# DSO_CPLD.net
KiCad netlist of a schematic drawn in Altium Designer
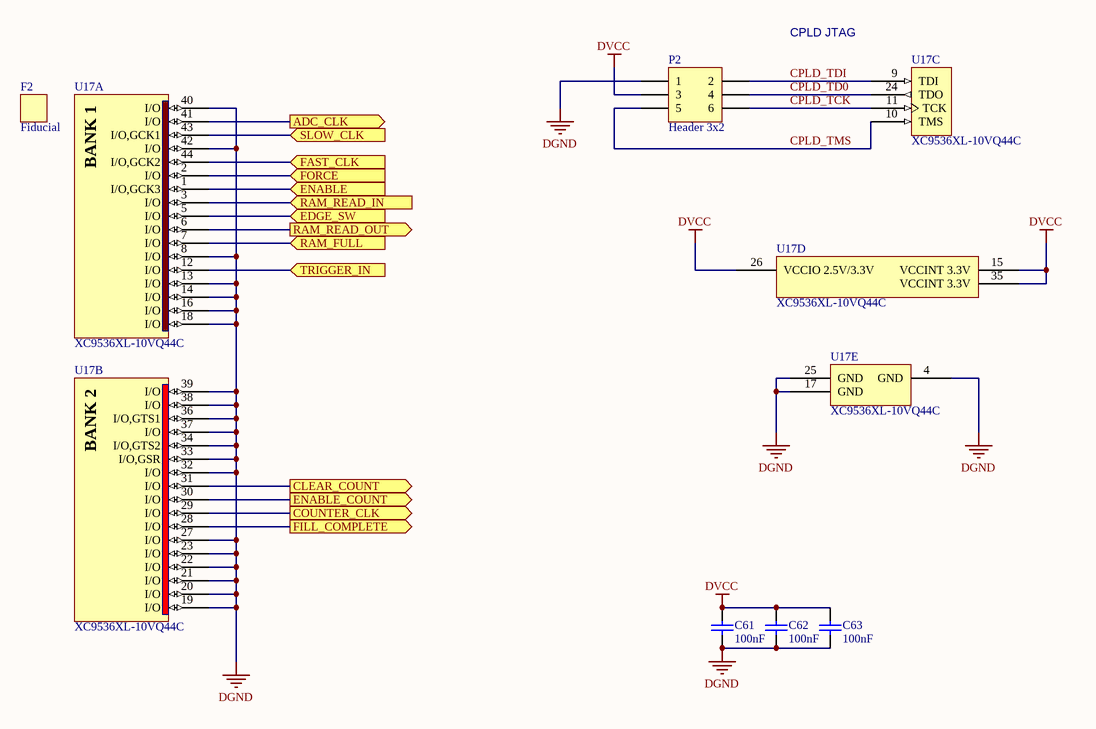
[diagram p0: DSO_CPLD.SchDoc]

(export (version "E")
  (design (tool "Eeschema 10.0.6"))
  (components
    (comp (ref "C61")
      (value "100nF")
      (footprint "0805C")
      (description "Capacitor")
      (fields (field (name "REVIEWED BY") "RM - 2018/08/05"))
      (libsource (lib "DSO") (part "C"))
    )
    (comp (ref "C62")
      (value "100nF")
      (footprint "0805C")
      (description "Capacitor")
      (fields (field (name "REVIEWED BY") "RM - 2018/08/05"))
      (libsource (lib "DSO") (part "C"))
    )
    (comp (ref "C63")
      (value "100nF")
      (footprint "0805C")
      (description "Capacitor")
      (fields (field (name "REVIEWED BY") "RM - 2018/08/05"))
      (libsource (lib "DSO") (part "C"))
    )
    (comp (ref "F2")
      (value "Fiducial")
      (footprint "FIDUCIAL")
      (description "Fiducial for pick and place machine")
      (libsource (lib "DSO") (part "Fiducial"))
    )
    (comp (ref "P2")
      (value "Header 3x2")
      (footprint "HDR3x2")
      (description "Header, 5-Pin")
      (fields (field (name "REVIEWED BY") "RM - 2018/08/05"))
      (libsource (lib "DSO") (part "Header 3x2"))
    )
    (comp (ref "U17")
      (value "XC9536XL-10VQ44C")
      (footprint "VQ44_L")
      (fields (field (name "REVIEWED BY") "RM - 2018/08/05"))
      (libsource (lib "DSO") (part "XC9536XL-10VQG44C"))
    )
  )
  (nets
    (net (code "1") (name "/ADC_CLK") (class "Default")
      (node (ref "U17") (pin "41") (pinfunction "I/O_41") (pintype "bidirectional"))
    )
    (net (code "2") (name "/CLEAR_COUNT") (class "Default")
      (node (ref "U17") (pin "31") (pinfunction "I/O_31") (pintype "bidirectional"))
    )
    (net (code "3") (name "/COUNTER_CLK") (class "Default")
      (node (ref "U17") (pin "29") (pinfunction "I/O_29") (pintype "bidirectional"))
    )
    (net (code "4") (name "/CPLD_TCK") (class "Default")
      (node (ref "P2") (pin "6") (pinfunction "6_6") (pintype "passive"))
      (node (ref "U17") (pin "11") (pinfunction "TCK_11") (pintype "input"))
    )
    (net (code "5") (name "/CPLD_TD0") (class "Default")
      (node (ref "P2") (pin "4") (pinfunction "4_4") (pintype "passive"))
      (node (ref "U17") (pin "24") (pinfunction "TDO_24") (pintype "output"))
    )
    (net (code "6") (name "/CPLD_TDI") (class "Default")
      (node (ref "P2") (pin "2") (pinfunction "2_2") (pintype "passive"))
      (node (ref "U17") (pin "9") (pinfunction "TDI_9") (pintype "input"))
    )
    (net (code "7") (name "/CPLD_TMS") (class "Default")
      (node (ref "P2") (pin "5") (pinfunction "5_5") (pintype "passive"))
      (node (ref "U17") (pin "10") (pinfunction "TMS_10") (pintype "input"))
    )
    (net (code "8") (name "/EDGE_SW") (class "Default")
      (node (ref "U17") (pin "5") (pinfunction "I/O_5") (pintype "bidirectional"))
    )
    (net (code "9") (name "/ENABLE") (class "Default")
      (node (ref "U17") (pin "1") (pinfunction "I/O,GCK3_1") (pintype "bidirectional"))
    )
    (net (code "10") (name "/ENABLE_COUNT") (class "Default")
      (node (ref "U17") (pin "30") (pinfunction "I/O_30") (pintype "bidirectional"))
    )
    (net (code "11") (name "/FAST_CLK") (class "Default")
      (node (ref "U17") (pin "44") (pinfunction "I/O,GCK2_44") (pintype "bidirectional"))
    )
    (net (code "12") (name "/FILL_COMPLETE") (class "Default")
      (node (ref "U17") (pin "28") (pinfunction "I/O_28") (pintype "bidirectional"))
    )
    (net (code "13") (name "/FORCE") (class "Default")
      (node (ref "U17") (pin "2") (pinfunction "I/O_2") (pintype "bidirectional"))
    )
    (net (code "14") (name "/RAM_FULL") (class "Default")
      (node (ref "U17") (pin "7") (pinfunction "I/O_7") (pintype "bidirectional"))
    )
    (net (code "15") (name "/RAM_READ_IN") (class "Default")
      (node (ref "U17") (pin "3") (pinfunction "I/O_3") (pintype "bidirectional"))
    )
    (net (code "16") (name "/RAM_READ_OUT") (class "Default")
      (node (ref "U17") (pin "6") (pinfunction "I/O_6") (pintype "bidirectional"))
    )
    (net (code "17") (name "/SLOW_CLK") (class "Default")
      (node (ref "U17") (pin "43") (pinfunction "I/O,GCK1_43") (pintype "bidirectional"))
    )
    (net (code "18") (name "/TRIGGER_IN") (class "Default")
      (node (ref "U17") (pin "12") (pinfunction "I/O_12") (pintype "bidirectional"))
    )
    (net (code "19") (name "DGND") (class "Default")
      (node (ref "C61") (pin "2") (pinfunction "2_2") (pintype "passive"))
      (node (ref "C62") (pin "2") (pinfunction "2_2") (pintype "passive"))
      (node (ref "C63") (pin "2") (pinfunction "2_2") (pintype "passive"))
      (node (ref "P2") (pin "1") (pinfunction "1_1") (pintype "passive"))
      (node (ref "U17") (pin "13") (pinfunction "I/O_13") (pintype "bidirectional"))
      (node (ref "U17") (pin "14") (pinfunction "I/O_14") (pintype "bidirectional"))
      (node (ref "U17") (pin "16") (pinfunction "I/O_16") (pintype "bidirectional"))
      (node (ref "U17") (pin "17") (pinfunction "GND_17") (pintype "power_in"))
      (node (ref "U17") (pin "18") (pinfunction "I/O_18") (pintype "bidirectional"))
      (node (ref "U17") (pin "19") (pinfunction "I/O_19") (pintype "bidirectional"))
      (node (ref "U17") (pin "20") (pinfunction "I/O_20") (pintype "bidirectional"))
      (node (ref "U17") (pin "21") (pinfunction "I/O_21") (pintype "bidirectional"))
      (node (ref "U17") (pin "22") (pinfunction "I/O_22") (pintype "bidirectional"))
      (node (ref "U17") (pin "23") (pinfunction "I/O_23") (pintype "bidirectional"))
      (node (ref "U17") (pin "25") (pinfunction "GND_25") (pintype "power_in"))
      (node (ref "U17") (pin "27") (pinfunction "I/O_27") (pintype "bidirectional"))
      (node (ref "U17") (pin "32") (pinfunction "I/O_32") (pintype "bidirectional"))
      (node (ref "U17") (pin "33") (pinfunction "I/O,GSR_33") (pintype "bidirectional"))
      (node (ref "U17") (pin "34") (pinfunction "I/O,GTS2_34") (pintype "bidirectional"))
      (node (ref "U17") (pin "36") (pinfunction "I/O,GTS1_36") (pintype "bidirectional"))
      (node (ref "U17") (pin "37") (pinfunction "I/O_37") (pintype "bidirectional"))
      (node (ref "U17") (pin "38") (pinfunction "I/O_38") (pintype "bidirectional"))
      (node (ref "U17") (pin "39") (pinfunction "I/O_39") (pintype "bidirectional"))
      (node (ref "U17") (pin "4") (pinfunction "GND_4") (pintype "power_in"))
      (node (ref "U17") (pin "40") (pinfunction "I/O_40") (pintype "bidirectional"))
      (node (ref "U17") (pin "42") (pinfunction "I/O_42") (pintype "bidirectional"))
      (node (ref "U17") (pin "8") (pinfunction "I/O_8") (pintype "bidirectional"))
    )
    (net (code "20") (name "DVCC") (class "Default")
      (node (ref "C61") (pin "1") (pinfunction "1_1") (pintype "passive"))
      (node (ref "C62") (pin "1") (pinfunction "1_1") (pintype "passive"))
      (node (ref "C63") (pin "1") (pinfunction "1_1") (pintype "passive"))
      (node (ref "P2") (pin "3") (pinfunction "3_3") (pintype "passive"))
      (node (ref "U17") (pin "15") (pinfunction "VCCINT_3.3V_15") (pintype "power_in"))
      (node (ref "U17") (pin "26") (pinfunction "VCCIO_2.5V/3.3V_26") (pintype "power_in"))
      (node (ref "U17") (pin "35") (pinfunction "VCCINT_3.3V_35") (pintype "power_in"))
    )
  )
)
